# Sheet1.net
KiCad netlist of a schematic drawn in Altium Designer
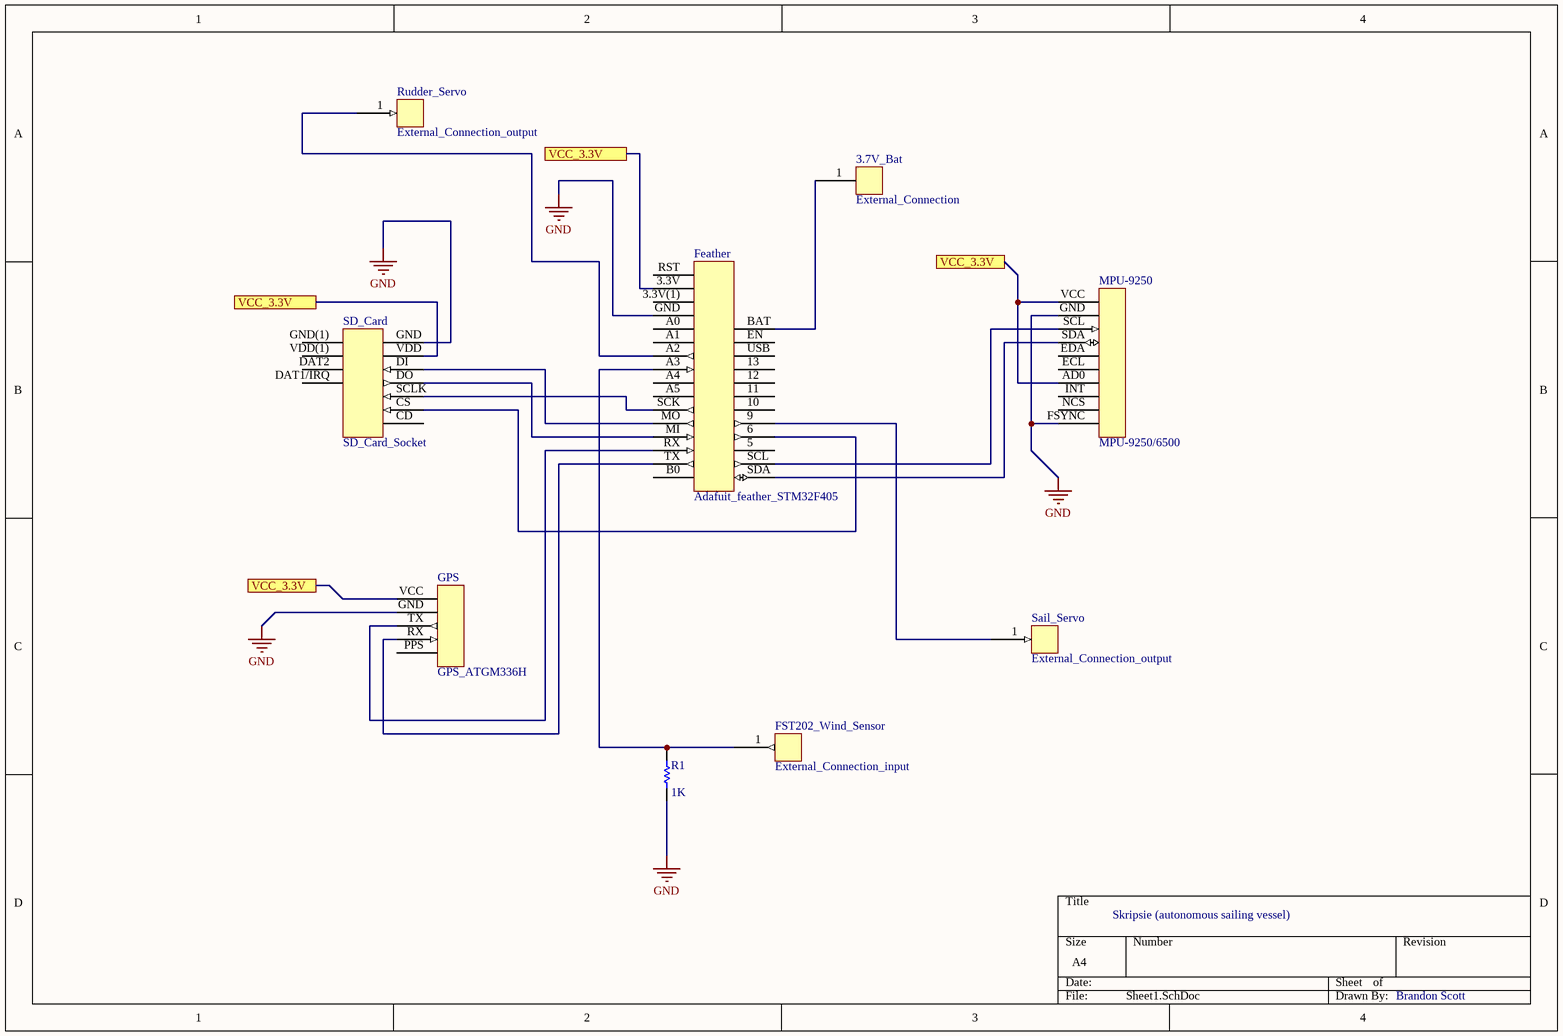
[diagram p0: Sheet1.SchDoc]

(export (version "E")
  (design (tool "Eeschema 10.0.6"))
  (components
    (comp (ref "3.7V_Bat")
      (value "External_Connection")
      (footprint "connector")
      (libsource (lib "Schlib1") (part "External_Connection"))
    )
    (comp (ref "Feather")
      (value "Adafuit_feather_STM32F405")
      (footprint "Adafuit_feather_STM32F405")
      (libsource (lib "Schlib1") (part "Adafuit_feather_STM32F405"))
    )
    (comp (ref "FST202_Wind_Sensor")
      (value "External_Connection_input")
      (footprint "connector")
      (libsource (lib "Schlib1") (part "External_Connection_input"))
    )
    (comp (ref "GPS")
      (value "GPS_ATGM336H")
      (footprint "GPS")
      (libsource (lib "Schlib1") (part "GPS_ATGM336H"))
    )
    (comp (ref "MPU-9250")
      (value "MPU-9250/6500")
      (footprint "MPU-9250/6500")
      (libsource (lib "Schlib1") (part "MPU-9250/6500"))
    )
    (comp (ref "R1")
      (value "1K")
      (footprint "AXIAL-0.3")
      (description "Resistor")
      (fields (field (name "Comment") "Res1") (field (name "PUBLISHER") "Altium Limited"))
      (libsource (lib "Miscellaneous Devices") (part "Res1"))
    )
    (comp (ref "Rudder_Servo")
      (value "External_Connection_output")
      (footprint "connector")
      (libsource (lib "Schlib1") (part "External_Connection_output"))
    )
    (comp (ref "Sail_Servo")
      (value "External_Connection_output")
      (footprint "connector")
      (libsource (lib "Schlib1") (part "External_Connection_output"))
    )
    (comp (ref "SD_Card")
      (value "SD_Card_Socket")
      (footprint "SD_Card_Socket")
      (libsource (lib "Schlib1") (part "SD_Card_Socket"))
    )
  )
  (nets
    (net (code "1") (name "/VCC_3.3V") (class "Default")
      (node (ref "Feather") (pin "3.3V") (pintype "power_in"))
      (node (ref "GPS") (pin "VCC") (pintype "power_in"))
      (node (ref "MPU-9250") (pin "AD0") (pintype "power_in"))
      (node (ref "MPU-9250") (pin "VCC") (pintype "power_in"))
      (node (ref "SD_Card") (pin "VDD") (pintype "power_in"))
    )
    (net (code "2") (name "GND") (class "Default")
      (node (ref "Feather") (pin "GND") (pintype "power_in"))
      (node (ref "GPS") (pin "GND") (pintype "power_in"))
      (node (ref "MPU-9250") (pin "FSYNC") (pintype "power_in"))
      (node (ref "MPU-9250") (pin "GND") (pintype "power_in"))
      (node (ref "R1") (pin "2") (pinfunction "2_2") (pintype "passive"))
      (node (ref "SD_Card") (pin "GND") (pintype "power_in"))
    )
    (net (code "3") (name "Net-(3.7V_Bat-Pad1)") (class "Default")
      (node (ref "3.7V_Bat") (pin "1") (pintype "power_in"))
      (node (ref "Feather") (pin "BAT") (pintype "power_in"))
    )
    (net (code "4") (name "Net-(FST202_Wind_Sensor-Pad1)") (class "Default")
      (node (ref "FST202_Wind_Sensor") (pin "1") (pintype "output"))
      (node (ref "Feather") (pin "A3") (pintype "input"))
      (node (ref "R1") (pin "1") (pinfunction "1_1") (pintype "passive"))
    )
    (net (code "5") (name "Net-(Feather-Pad6)") (class "Default")
      (node (ref "Feather") (pin "6") (pintype "output"))
      (node (ref "SD_Card") (pin "CS") (pintype "input"))
    )
    (net (code "6") (name "Net-(Feather-Pad9)") (class "Default")
      (node (ref "Feather") (pin "9") (pintype "output"))
      (node (ref "Sail_Servo") (pin "1") (pintype "input"))
    )
    (net (code "7") (name "Net-(Feather-PadA2)") (class "Default")
      (node (ref "Feather") (pin "A2") (pintype "output"))
      (node (ref "Rudder_Servo") (pin "1") (pintype "input"))
    )
    (net (code "8") (name "Net-(Feather-PadMI)") (class "Default")
      (node (ref "Feather") (pin "MI") (pintype "input"))
      (node (ref "SD_Card") (pin "DO") (pintype "output"))
    )
    (net (code "9") (name "Net-(Feather-PadMO)") (class "Default")
      (node (ref "Feather") (pin "MO") (pintype "output"))
      (node (ref "SD_Card") (pin "DI") (pintype "input"))
    )
    (net (code "10") (name "Net-(Feather-PadRX)") (class "Default")
      (node (ref "Feather") (pin "RX") (pintype "input"))
      (node (ref "GPS") (pin "TX") (pintype "output"))
    )
    (net (code "11") (name "Net-(Feather-PadSCK)") (class "Default")
      (node (ref "Feather") (pin "SCK") (pintype "output"))
      (node (ref "SD_Card") (pin "SCLK") (pintype "input"))
    )
    (net (code "12") (name "Net-(Feather-PadSCL)") (class "Default")
      (node (ref "Feather") (pin "SCL") (pintype "output"))
      (node (ref "MPU-9250") (pin "SCL") (pintype "input"))
    )
    (net (code "13") (name "Net-(Feather-PadSDA)") (class "Default")
      (node (ref "Feather") (pin "SDA") (pintype "bidirectional"))
      (node (ref "MPU-9250") (pin "SDA") (pintype "bidirectional"))
    )
    (net (code "14") (name "Net-(Feather-PadTX)") (class "Default")
      (node (ref "Feather") (pin "TX") (pintype "output"))
      (node (ref "GPS") (pin "RX") (pintype "input"))
    )
    (net (code "15") (name "unconnected-(Feather-Pad3.3V(1))") (class "Default")
      (node (ref "Feather") (pin "3.3V(1)") (pintype "passive"))
    )
    (net (code "16") (name "unconnected-(Feather-Pad5)") (class "Default")
      (node (ref "Feather") (pin "5") (pintype "passive"))
    )
    (net (code "17") (name "unconnected-(Feather-Pad10)") (class "Default")
      (node (ref "Feather") (pin "10") (pintype "passive"))
    )
    (net (code "18") (name "unconnected-(Feather-Pad11)") (class "Default")
      (node (ref "Feather") (pin "11") (pintype "passive"))
    )
    (net (code "19") (name "unconnected-(Feather-Pad12)") (class "Default")
      (node (ref "Feather") (pin "12") (pintype "passive"))
    )
    (net (code "20") (name "unconnected-(Feather-Pad13)") (class "Default")
      (node (ref "Feather") (pin "13") (pintype "passive"))
    )
    (net (code "21") (name "unconnected-(Feather-PadA0)") (class "Default")
      (node (ref "Feather") (pin "A0") (pintype "passive"))
    )
    (net (code "22") (name "unconnected-(Feather-PadA1)") (class "Default")
      (node (ref "Feather") (pin "A1") (pintype "passive"))
    )
    (net (code "23") (name "unconnected-(Feather-PadA4)") (class "Default")
      (node (ref "Feather") (pin "A4") (pintype "passive"))
    )
    (net (code "24") (name "unconnected-(Feather-PadA5)") (class "Default")
      (node (ref "Feather") (pin "A5") (pintype "passive"))
    )
    (net (code "25") (name "unconnected-(Feather-PadB0)") (class "Default")
      (node (ref "Feather") (pin "B0") (pintype "passive"))
    )
    (net (code "26") (name "unconnected-(Feather-PadEN)") (class "Default")
      (node (ref "Feather") (pin "EN") (pintype "passive"))
    )
    (net (code "27") (name "unconnected-(Feather-PadRST)") (class "Default")
      (node (ref "Feather") (pin "RST") (pintype "passive"))
    )
    (net (code "28") (name "unconnected-(Feather-PadUSB)") (class "Default")
      (node (ref "Feather") (pin "USB") (pintype "passive"))
    )
    (net (code "29") (name "unconnected-(GPS-PadPPS)") (class "Default")
      (node (ref "GPS") (pin "PPS") (pintype "passive"))
    )
    (net (code "30") (name "unconnected-(MPU-9250-PadECL)") (class "Default")
      (node (ref "MPU-9250") (pin "ECL") (pintype "passive"))
    )
    (net (code "31") (name "unconnected-(MPU-9250-PadEDA)") (class "Default")
      (node (ref "MPU-9250") (pin "EDA") (pintype "passive"))
    )
    (net (code "32") (name "unconnected-(MPU-9250-PadINT)") (class "Default")
      (node (ref "MPU-9250") (pin "INT") (pintype "passive"))
    )
    (net (code "33") (name "unconnected-(MPU-9250-PadNCS)") (class "Default")
      (node (ref "MPU-9250") (pin "NCS") (pintype "passive"))
    )
    (net (code "34") (name "unconnected-(SD_Card-PadCD)") (class "Default")
      (node (ref "SD_Card") (pin "CD") (pintype "passive"))
    )
    (net (code "35") (name "unconnected-(SD_Card-PadDAT1{slash}IRQ)") (class "Default")
      (node (ref "SD_Card") (pin "DAT1/IRQ") (pintype "passive"))
    )
    (net (code "36") (name "unconnected-(SD_Card-PadDAT2)") (class "Default")
      (node (ref "SD_Card") (pin "DAT2") (pintype "passive"))
    )
    (net (code "37") (name "unconnected-(SD_Card-PadGND(1))") (class "Default")
      (node (ref "SD_Card") (pin "GND(1)") (pintype "passive"))
    )
    (net (code "38") (name "unconnected-(SD_Card-PadVDD(1))") (class "Default")
      (node (ref "SD_Card") (pin "VDD(1)") (pintype "passive"))
    )
  )
)
